# pilot.net
KiCad netlist of a schematic drawn in EAGLE
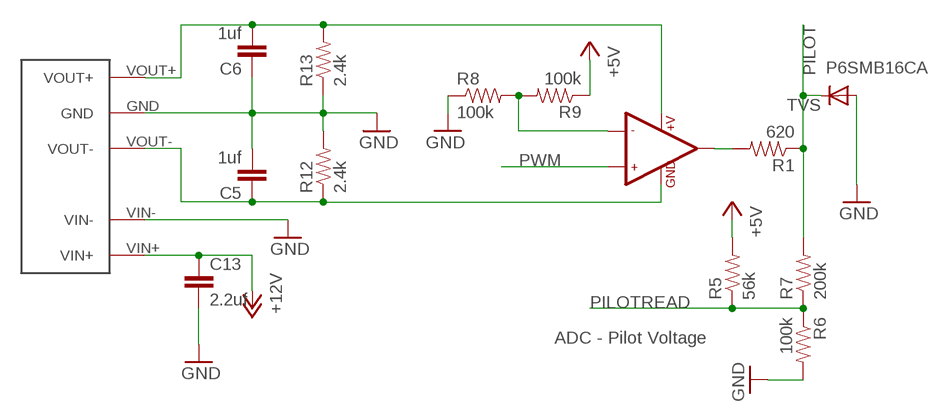
[diagram p0: schematic, sheet 1]

(export (version "E")
  (design (tool "Eeschema 10.0.6"))
  (components
    (comp (ref "C5")
      (value "1uf")
      (footprint "eagle-import:0805")
      (libsource (lib "eagle-import") (part "CAP0805"))
    )
    (comp (ref "C6")
      (value "1uf")
      (footprint "eagle-import:0805")
      (libsource (lib "eagle-import") (part "CAP0805"))
    )
    (comp (ref "C13")
      (value "2.2uf")
      (footprint "eagle-import:0805")
      (libsource (lib "eagle-import") (part "CAP0805"))
    )
    (comp (ref "DCDC")
      (value "MD112D-12E")
      (footprint "eagle-import:DCDC_SIP")
      (libsource (lib "eagle-import") (part "DCDC_SIP"))
    )
    (comp (ref "IC4")
      (value "LF353")
      (footprint "eagle-import:SO08")
      (libsource (lib "eagle-import") (part "LMV358"))
    )
    (comp (ref "R1")
      (value "620")
      (footprint "eagle-import:0805")
      (libsource (lib "eagle-import") (part "RESISTOR0805-RES"))
    )
    (comp (ref "R5")
      (value "56k")
      (footprint "eagle-import:0805")
      (libsource (lib "eagle-import") (part "RESISTOR0805-RES"))
    )
    (comp (ref "R6")
      (value "100k")
      (footprint "eagle-import:0805")
      (libsource (lib "eagle-import") (part "RESISTOR0805-RES"))
    )
    (comp (ref "R7")
      (value "200k")
      (footprint "eagle-import:0805")
      (libsource (lib "eagle-import") (part "RESISTOR0805-RES"))
    )
    (comp (ref "R8")
      (value "100k")
      (footprint "eagle-import:0805")
      (libsource (lib "eagle-import") (part "RESISTOR0805-RES"))
    )
    (comp (ref "R9")
      (value "100k")
      (footprint "eagle-import:0805")
      (libsource (lib "eagle-import") (part "RESISTOR0805-RES"))
    )
    (comp (ref "R12")
      (value "2.4k")
      (footprint "eagle-import:0805")
      (libsource (lib "eagle-import") (part "RESISTOR0805-RES"))
    )
    (comp (ref "R13")
      (value "2.4k")
      (footprint "eagle-import:0805")
      (libsource (lib "eagle-import") (part "RESISTOR0805-RES"))
    )
    (comp (ref "TVS")
      (value "P6SMB16CA")
      (footprint "eagle-import:SMB")
      (libsource (lib "eagle-import") (part "DIODE-SMB"))
    )
  )
  (nets
    (net (code "1") (name "+5V") (class "Default")
      (node (ref "R5") (pin "2") (pinfunction "2_2") (pintype "passive"))
      (node (ref "R9") (pin "1") (pinfunction "1_1") (pintype "passive"))
    )
    (net (code "2") (name "+12V") (class "Default")
      (node (ref "C13") (pin "1") (pinfunction "1_1") (pintype "passive"))
      (node (ref "DCDC") (pin "VIN+") (pinfunction "VIN+_VIN+") (pintype "bidirectional"))
    )
    (net (code "3") (name "/PILOT") (class "Default")
      (node (ref "R1") (pin "1") (pinfunction "1_1") (pintype "passive"))
      (node (ref "R7") (pin "2") (pinfunction "2_2") (pintype "passive"))
      (node (ref "TVS") (pin "C") (pinfunction "C_C") (pintype "passive"))
    )
    (net (code "4") (name "/PILOTREAD") (class "Default")
      (node (ref "R5") (pin "1") (pinfunction "1_1") (pintype "passive"))
      (node (ref "R6") (pin "1") (pinfunction "1_1") (pintype "passive"))
      (node (ref "R7") (pin "1") (pinfunction "1_1") (pintype "passive"))
    )
    (net (code "5") (name "/PWM") (class "Default")
      (node (ref "IC4") (pin "3") (pinfunction "+IN1_3") (pintype "input"))
    )
    (net (code "6") (name "GND") (class "Default")
      (node (ref "C13") (pin "2") (pinfunction "2_2") (pintype "passive"))
      (node (ref "C5") (pin "2") (pinfunction "2_2") (pintype "passive"))
      (node (ref "C6") (pin "1") (pinfunction "1_1") (pintype "passive"))
      (node (ref "DCDC") (pin "GND") (pinfunction "GND_GND") (pintype "bidirectional"))
      (node (ref "DCDC") (pin "VIN-") (pinfunction "VIN-_VIN-") (pintype "bidirectional"))
      (node (ref "R12") (pin "2") (pinfunction "2_2") (pintype "passive"))
      (node (ref "R13") (pin "1") (pinfunction "1_1") (pintype "passive"))
      (node (ref "R6") (pin "2") (pinfunction "2_2") (pintype "passive"))
      (node (ref "R8") (pin "1") (pinfunction "1_1") (pintype "passive"))
      (node (ref "TVS") (pin "A") (pinfunction "A_A") (pintype "passive"))
    )
    (net (code "7") (name "Net-(IC4A-+V)") (class "Default")
      (node (ref "C6") (pin "2") (pinfunction "2_2") (pintype "passive"))
      (node (ref "DCDC") (pin "VOUT+") (pinfunction "VOUT+_VOUT+") (pintype "bidirectional"))
      (node (ref "IC4") (pin "8") (pinfunction "+V_8") (pintype "power_in"))
      (node (ref "R13") (pin "2") (pinfunction "2_2") (pintype "passive"))
    )
    (net (code "8") (name "Net-(IC4A--IN1)") (class "Default")
      (node (ref "IC4") (pin "2") (pinfunction "-IN1_2") (pintype "input"))
      (node (ref "R8") (pin "2") (pinfunction "2_2") (pintype "passive"))
      (node (ref "R9") (pin "2") (pinfunction "2_2") (pintype "passive"))
    )
    (net (code "9") (name "Net-(IC4A-GND)") (class "Default")
      (node (ref "C5") (pin "1") (pinfunction "1_1") (pintype "passive"))
      (node (ref "DCDC") (pin "VOUT-") (pinfunction "VOUT-_VOUT-") (pintype "bidirectional"))
      (node (ref "IC4") (pin "4") (pinfunction "GND_4") (pintype "power_in"))
      (node (ref "R12") (pin "1") (pinfunction "1_1") (pintype "passive"))
    )
    (net (code "10") (name "Net-(IC4A-OUT1)") (class "Default")
      (node (ref "IC4") (pin "1") (pinfunction "OUT1_1") (pintype "output"))
      (node (ref "R1") (pin "2") (pinfunction "2_2") (pintype "passive"))
    )
  )
)
